# 2_NZPP.net
KiCad netlist of a schematic drawn in Altium Designer
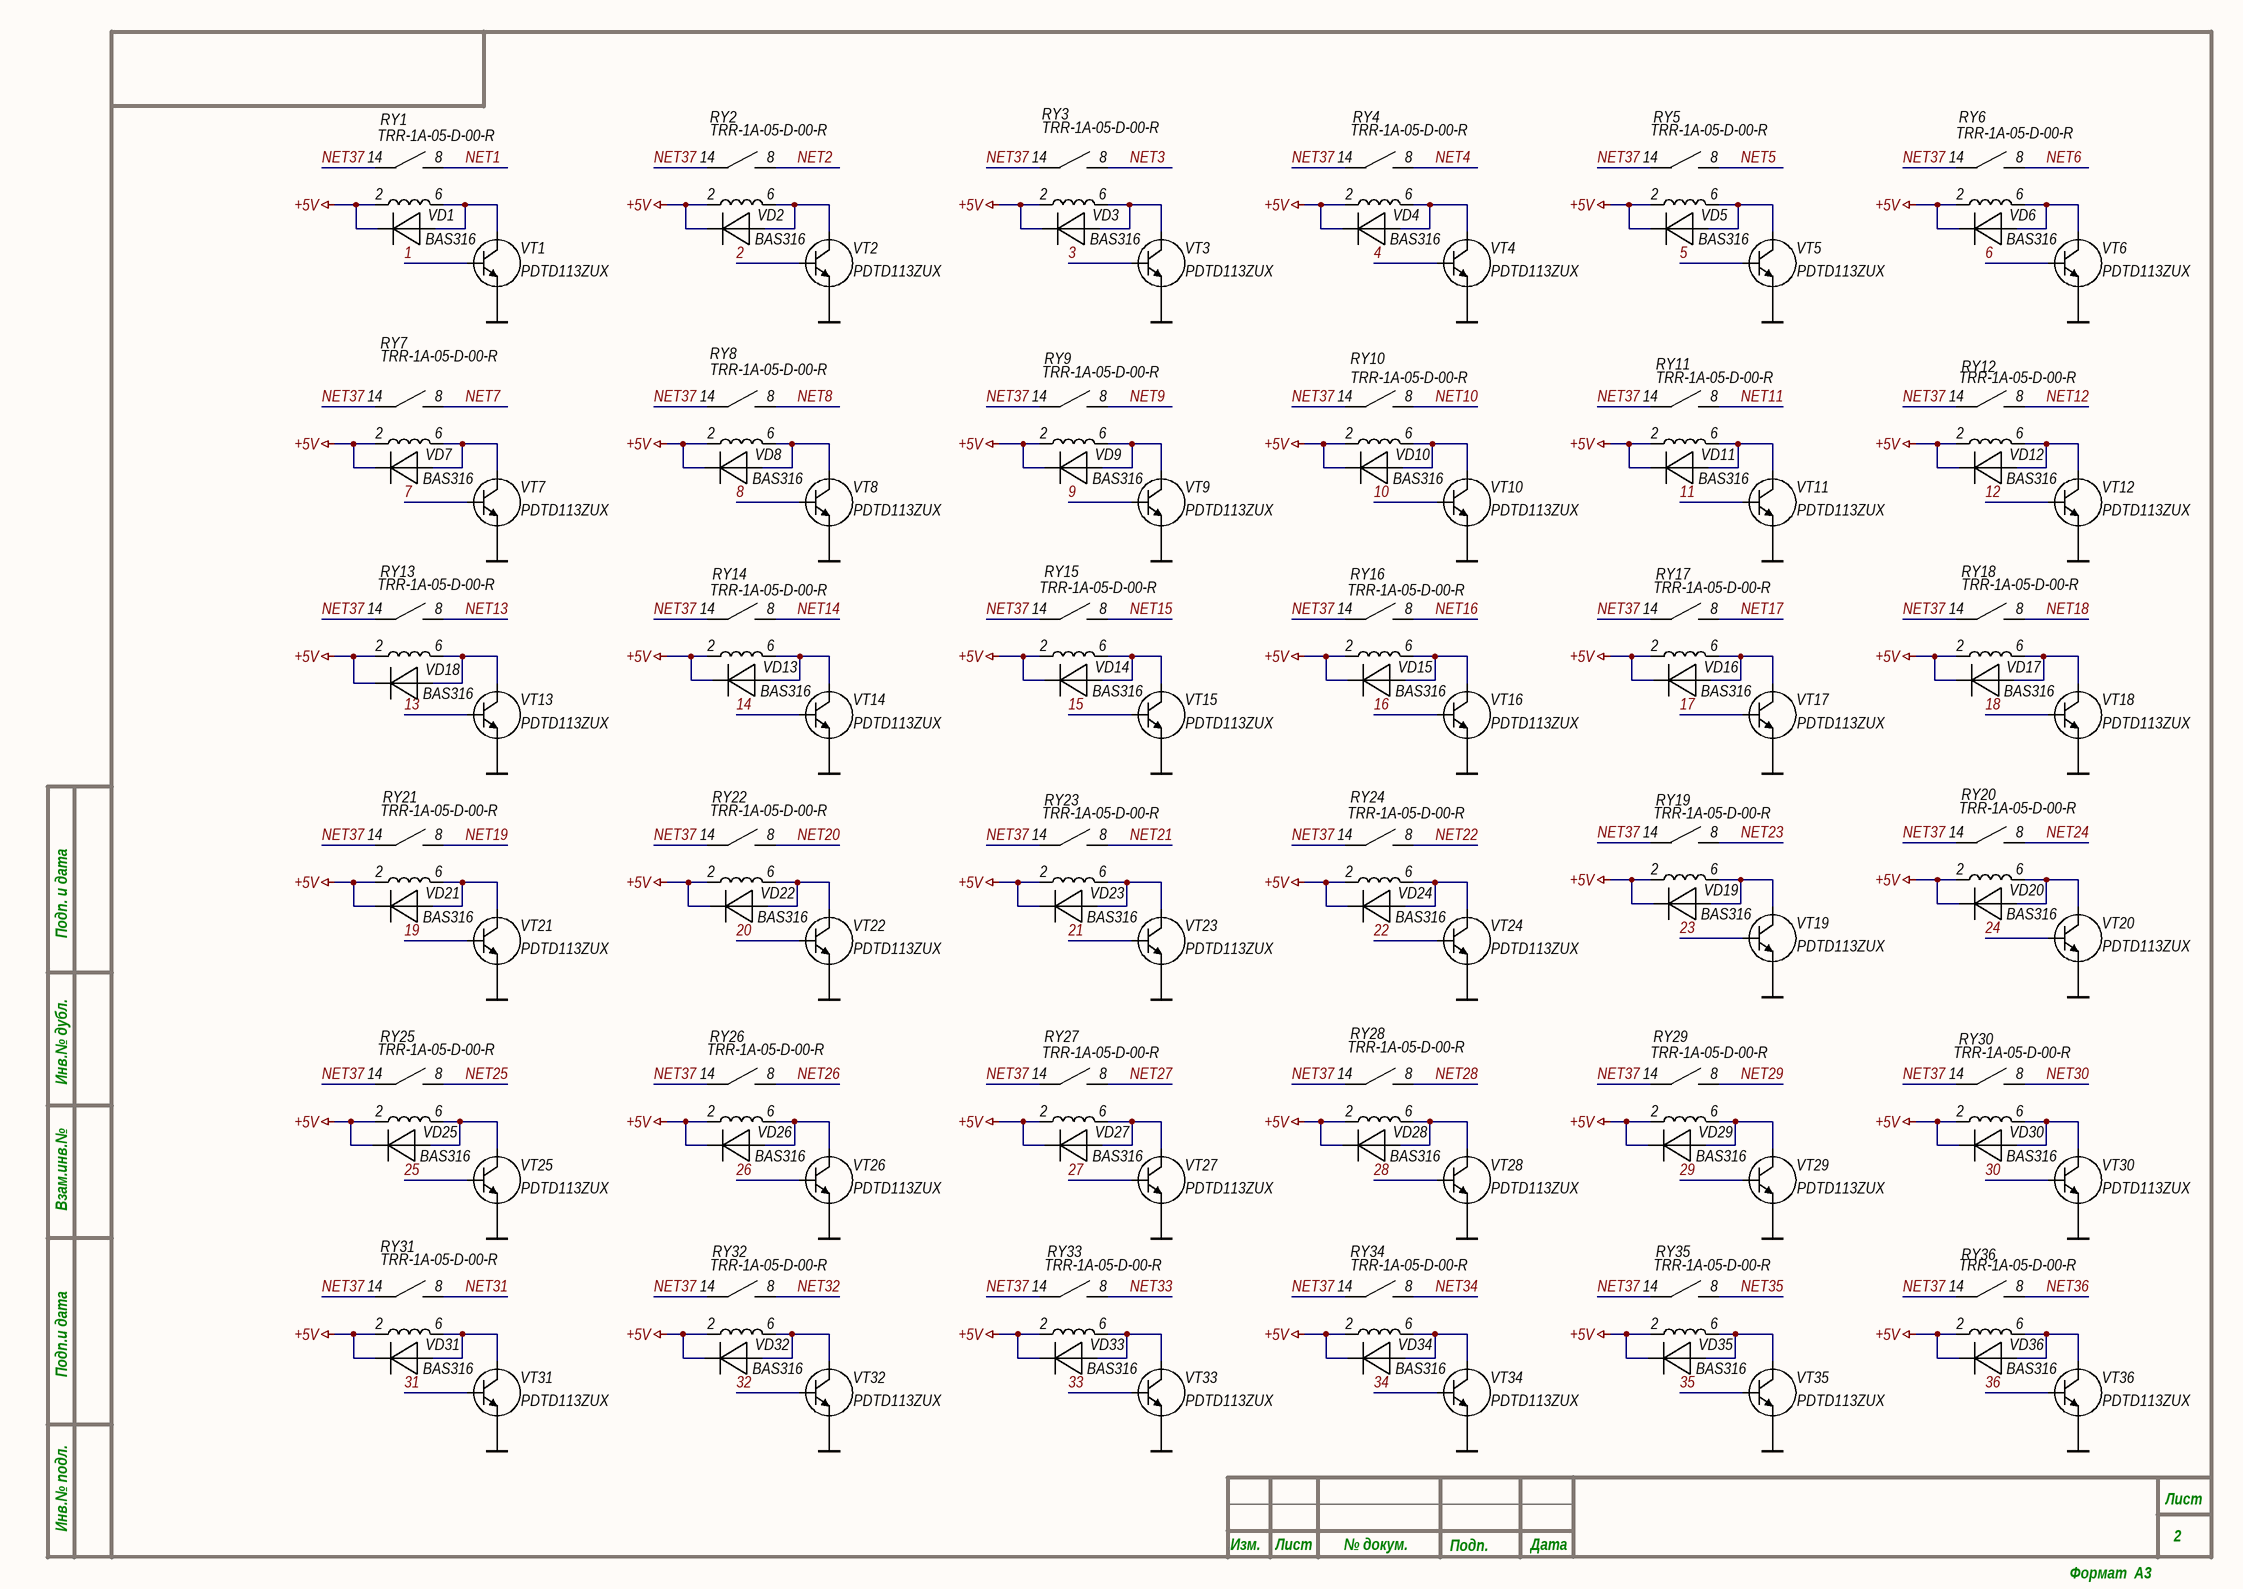
[diagram p0: 2.NZPP.SchDoc]

(export (version "E")
  (design (tool "Eeschema 10.0.6"))
  (components
    (comp (ref "RY1")
      (value "TRR-1A-05-D-00-R")
      (footprint "TRR-1A-05-D-00-R")
      (libsource (lib "Schlib1") (part "TRR-1A-05-D-00-R"))
    )
    (comp (ref "RY2")
      (value "TRR-1A-05-D-00-R")
      (footprint "TRR-1A-05-D-00-R")
      (libsource (lib "Schlib1") (part "TRR-1A-05-D-00-R"))
    )
    (comp (ref "RY3")
      (value "TRR-1A-05-D-00-R")
      (footprint "TRR-1A-05-D-00-R")
      (libsource (lib "Schlib1") (part "TRR-1A-05-D-00-R"))
    )
    (comp (ref "RY4")
      (value "TRR-1A-05-D-00-R")
      (footprint "TRR-1A-05-D-00-R")
      (libsource (lib "Schlib1") (part "TRR-1A-05-D-00-R"))
    )
    (comp (ref "RY5")
      (value "TRR-1A-05-D-00-R")
      (footprint "TRR-1A-05-D-00-R")
      (libsource (lib "Schlib1") (part "TRR-1A-05-D-00-R"))
    )
    (comp (ref "RY6")
      (value "TRR-1A-05-D-00-R")
      (footprint "TRR-1A-05-D-00-R")
      (libsource (lib "") (part "TRR-1A-05-D-00-R_1"))
    )
    (comp (ref "RY7")
      (value "TRR-1A-05-D-00-R")
      (footprint "TRR-1A-05-D-00-R")
      (libsource (lib "Schlib1") (part "TRR-1A-05-D-00-R"))
    )
    (comp (ref "RY8")
      (value "TRR-1A-05-D-00-R")
      (footprint "TRR-1A-05-D-00-R")
      (libsource (lib "Schlib1") (part "TRR-1A-05-D-00-R"))
    )
    (comp (ref "RY9")
      (value "TRR-1A-05-D-00-R")
      (footprint "TRR-1A-05-D-00-R")
      (libsource (lib "Schlib1") (part "TRR-1A-05-D-00-R"))
    )
    (comp (ref "RY10")
      (value "TRR-1A-05-D-00-R")
      (footprint "TRR-1A-05-D-00-R")
      (libsource (lib "Schlib1") (part "TRR-1A-05-D-00-R"))
    )
    (comp (ref "RY11")
      (value "TRR-1A-05-D-00-R")
      (footprint "TRR-1A-05-D-00-R")
      (libsource (lib "Schlib1") (part "TRR-1A-05-D-00-R"))
    )
    (comp (ref "RY12")
      (value "TRR-1A-05-D-00-R")
      (footprint "TRR-1A-05-D-00-R")
      (libsource (lib "") (part "TRR-1A-05-D-00-R_1"))
    )
    (comp (ref "RY13")
      (value "TRR-1A-05-D-00-R")
      (footprint "TRR-1A-05-D-00-R")
      (libsource (lib "Schlib1") (part "TRR-1A-05-D-00-R"))
    )
    (comp (ref "RY14")
      (value "TRR-1A-05-D-00-R")
      (footprint "TRR-1A-05-D-00-R")
      (libsource (lib "Schlib1") (part "TRR-1A-05-D-00-R"))
    )
    (comp (ref "RY15")
      (value "TRR-1A-05-D-00-R")
      (footprint "TRR-1A-05-D-00-R")
      (libsource (lib "Schlib1") (part "TRR-1A-05-D-00-R"))
    )
    (comp (ref "RY16")
      (value "TRR-1A-05-D-00-R")
      (footprint "TRR-1A-05-D-00-R")
      (libsource (lib "Schlib1") (part "TRR-1A-05-D-00-R"))
    )
    (comp (ref "RY17")
      (value "TRR-1A-05-D-00-R")
      (footprint "TRR-1A-05-D-00-R")
      (libsource (lib "Schlib1") (part "TRR-1A-05-D-00-R"))
    )
    (comp (ref "RY18")
      (value "TRR-1A-05-D-00-R")
      (footprint "TRR-1A-05-D-00-R")
      (libsource (lib "") (part "TRR-1A-05-D-00-R_1"))
    )
    (comp (ref "RY19")
      (value "TRR-1A-05-D-00-R")
      (footprint "TRR-1A-05-D-00-R")
      (libsource (lib "Schlib1") (part "TRR-1A-05-D-00-R"))
    )
    (comp (ref "RY20")
      (value "TRR-1A-05-D-00-R")
      (footprint "TRR-1A-05-D-00-R")
      (libsource (lib "") (part "TRR-1A-05-D-00-R_1"))
    )
    (comp (ref "RY21")
      (value "TRR-1A-05-D-00-R")
      (footprint "TRR-1A-05-D-00-R")
      (libsource (lib "Schlib1") (part "TRR-1A-05-D-00-R"))
    )
    (comp (ref "RY22")
      (value "TRR-1A-05-D-00-R")
      (footprint "TRR-1A-05-D-00-R")
      (libsource (lib "Schlib1") (part "TRR-1A-05-D-00-R"))
    )
    (comp (ref "RY23")
      (value "TRR-1A-05-D-00-R")
      (footprint "TRR-1A-05-D-00-R")
      (libsource (lib "Schlib1") (part "TRR-1A-05-D-00-R"))
    )
    (comp (ref "RY24")
      (value "TRR-1A-05-D-00-R")
      (footprint "TRR-1A-05-D-00-R")
      (libsource (lib "Schlib1") (part "TRR-1A-05-D-00-R"))
    )
    (comp (ref "RY25")
      (value "TRR-1A-05-D-00-R")
      (footprint "TRR-1A-05-D-00-R")
      (libsource (lib "Schlib1") (part "TRR-1A-05-D-00-R"))
    )
    (comp (ref "RY26")
      (value "TRR-1A-05-D-00-R")
      (footprint "TRR-1A-05-D-00-R")
      (libsource (lib "Schlib1") (part "TRR-1A-05-D-00-R"))
    )
    (comp (ref "RY27")
      (value "TRR-1A-05-D-00-R")
      (footprint "TRR-1A-05-D-00-R")
      (libsource (lib "Schlib1") (part "TRR-1A-05-D-00-R"))
    )
    (comp (ref "RY28")
      (value "TRR-1A-05-D-00-R")
      (footprint "TRR-1A-05-D-00-R")
      (libsource (lib "Schlib1") (part "TRR-1A-05-D-00-R"))
    )
    (comp (ref "RY29")
      (value "TRR-1A-05-D-00-R")
      (footprint "TRR-1A-05-D-00-R")
      (libsource (lib "Schlib1") (part "TRR-1A-05-D-00-R"))
    )
    (comp (ref "RY30")
      (value "TRR-1A-05-D-00-R")
      (footprint "TRR-1A-05-D-00-R")
      (libsource (lib "") (part "TRR-1A-05-D-00-R_1"))
    )
    (comp (ref "RY31")
      (value "TRR-1A-05-D-00-R")
      (footprint "TRR-1A-05-D-00-R")
      (libsource (lib "Schlib1") (part "TRR-1A-05-D-00-R"))
    )
    (comp (ref "RY32")
      (value "TRR-1A-05-D-00-R")
      (footprint "TRR-1A-05-D-00-R")
      (libsource (lib "Schlib1") (part "TRR-1A-05-D-00-R"))
    )
    (comp (ref "RY33")
      (value "TRR-1A-05-D-00-R")
      (footprint "TRR-1A-05-D-00-R")
      (libsource (lib "Schlib1") (part "TRR-1A-05-D-00-R"))
    )
    (comp (ref "RY34")
      (value "TRR-1A-05-D-00-R")
      (footprint "TRR-1A-05-D-00-R")
      (libsource (lib "Schlib1") (part "TRR-1A-05-D-00-R"))
    )
    (comp (ref "RY35")
      (value "TRR-1A-05-D-00-R")
      (footprint "TRR-1A-05-D-00-R")
      (libsource (lib "Schlib1") (part "TRR-1A-05-D-00-R"))
    )
    (comp (ref "RY36")
      (value "TRR-1A-05-D-00-R")
      (footprint "TRR-1A-05-D-00-R")
      (libsource (lib "") (part "TRR-1A-05-D-00-R_1"))
    )
    (comp (ref "VD1")
      (value "BAS316")
      (footprint "DIODE: SOD323")
      (libsource (lib "diode") (part "Diode_single"))
    )
    (comp (ref "VD2")
      (value "BAS316")
      (footprint "DIODE: SOD323")
      (libsource (lib "diode") (part "Diode_single"))
    )
    (comp (ref "VD3")
      (value "BAS316")
      (footprint "DIODE: SOD323")
      (libsource (lib "diode") (part "Diode_single"))
    )
    (comp (ref "VD4")
      (value "BAS316")
      (footprint "DIODE: SOD323")
      (libsource (lib "diode") (part "Diode_single"))
    )
    (comp (ref "VD5")
      (value "BAS316")
      (footprint "DIODE: SOD323")
      (libsource (lib "diode") (part "Diode_single"))
    )
    (comp (ref "VD6")
      (value "BAS316")
      (footprint "DIODE: SOD323")
      (libsource (lib "diode") (part "Diode_single"))
    )
    (comp (ref "VD7")
      (value "BAS316")
      (footprint "DIODE: SOD323")
      (libsource (lib "diode") (part "Diode_single"))
    )
    (comp (ref "VD8")
      (value "BAS316")
      (footprint "DIODE: SOD323")
      (libsource (lib "diode") (part "Diode_single"))
    )
    (comp (ref "VD9")
      (value "BAS316")
      (footprint "DIODE: SOD323")
      (libsource (lib "diode") (part "Diode_single"))
    )
    (comp (ref "VD10")
      (value "BAS316")
      (footprint "DIODE: SOD323")
      (libsource (lib "diode") (part "Diode_single"))
    )
    (comp (ref "VD11")
      (value "BAS316")
      (footprint "DIODE: SOD323")
      (libsource (lib "diode") (part "Diode_single"))
    )
    (comp (ref "VD12")
      (value "BAS316")
      (footprint "DIODE: SOD323")
      (libsource (lib "diode") (part "Diode_single"))
    )
    (comp (ref "VD13")
      (value "BAS316")
      (footprint "DIODE: SOD323")
      (libsource (lib "diode") (part "Diode_single"))
    )
    (comp (ref "VD14")
      (value "BAS316")
      (footprint "DIODE: SOD323")
      (libsource (lib "diode") (part "Diode_single"))
    )
    (comp (ref "VD15")
      (value "BAS316")
      (footprint "DIODE: SOD323")
      (libsource (lib "diode") (part "Diode_single"))
    )
    (comp (ref "VD16")
      (value "BAS316")
      (footprint "DIODE: SOD323")
      (libsource (lib "diode") (part "Diode_single"))
    )
    (comp (ref "VD17")
      (value "BAS316")
      (footprint "DIODE: SOD323")
      (libsource (lib "diode") (part "Diode_single"))
    )
    (comp (ref "VD18")
      (value "BAS316")
      (footprint "DIODE: SOD323")
      (libsource (lib "diode") (part "Diode_single"))
    )
    (comp (ref "VD19")
      (value "BAS316")
      (footprint "DIODE: SOD323")
      (libsource (lib "diode") (part "Diode_single"))
    )
    (comp (ref "VD20")
      (value "BAS316")
      (footprint "DIODE: SOD323")
      (libsource (lib "diode") (part "Diode_single"))
    )
    (comp (ref "VD21")
      (value "BAS316")
      (footprint "DIODE: SOD323")
      (libsource (lib "diode") (part "Diode_single"))
    )
    (comp (ref "VD22")
      (value "BAS316")
      (footprint "DIODE: SOD323")
      (libsource (lib "diode") (part "Diode_single"))
    )
    (comp (ref "VD23")
      (value "BAS316")
      (footprint "DIODE: SOD323")
      (libsource (lib "diode") (part "Diode_single"))
    )
    (comp (ref "VD24")
      (value "BAS316")
      (footprint "DIODE: SOD323")
      (libsource (lib "diode") (part "Diode_single"))
    )
    (comp (ref "VD25")
      (value "BAS316")
      (footprint "DIODE: SOD323")
      (libsource (lib "diode") (part "Diode_single"))
    )
    (comp (ref "VD26")
      (value "BAS316")
      (footprint "DIODE: SOD323")
      (libsource (lib "diode") (part "Diode_single"))
    )
    (comp (ref "VD27")
      (value "BAS316")
      (footprint "DIODE: SOD323")
      (libsource (lib "diode") (part "Diode_single"))
    )
    (comp (ref "VD28")
      (value "BAS316")
      (footprint "DIODE: SOD323")
      (libsource (lib "") (part "Diode_single_1"))
    )
    (comp (ref "VD29")
      (value "BAS316")
      (footprint "DIODE: SOD323")
      (libsource (lib "diode") (part "Diode_single"))
    )
    (comp (ref "VD30")
      (value "BAS316")
      (footprint "DIODE: SOD323")
      (libsource (lib "diode") (part "Diode_single"))
    )
    (comp (ref "VD31")
      (value "BAS316")
      (footprint "DIODE: SOD323")
      (libsource (lib "diode") (part "Diode_single"))
    )
    (comp (ref "VD32")
      (value "BAS316")
      (footprint "DIODE: SOD323")
      (libsource (lib "diode") (part "Diode_single"))
    )
    (comp (ref "VD33")
      (value "BAS316")
      (footprint "DIODE: SOD323")
      (libsource (lib "diode") (part "Diode_single"))
    )
    (comp (ref "VD34")
      (value "BAS316")
      (footprint "DIODE: SOD323")
      (libsource (lib "diode") (part "Diode_single"))
    )
    (comp (ref "VD35")
      (value "BAS316")
      (footprint "DIODE: SOD323")
      (libsource (lib "diode") (part "Diode_single"))
    )
    (comp (ref "VD36")
      (value "BAS316")
      (footprint "DIODE: SOD323")
      (libsource (lib "diode") (part "Diode_single"))
    )
    (comp (ref "VT1")
      (value "PDTD113ZUX")
      (footprint "SC-70")
      (fields
        (field (name "MANUFACTURER") "ON Semiconductor")
        (field (name "VALUEMANUFACTURERPARTNUMBER") "NPN transistor, 45V, 100mA, 100MHz, 300mW, 0.6V, 420, SOT-23, -55...+125°C")
        (field (name "PARTNUMBER") "PDTD113ZUX")
      )
      (libsource (lib "transistor") (part "BJT_NPN_132"))
    )
    (comp (ref "VT2")
      (value "PDTD113ZUX")
      (footprint "SC-70")
      (fields
        (field (name "MANUFACTURER") "ON Semiconductor")
        (field (name "VALUEMANUFACTURERPARTNUMBER") "NPN transistor, 45V, 100mA, 100MHz, 300mW, 0.6V, 420, SOT-23, -55...+125°C")
        (field (name "PARTNUMBER") "PDTD113ZUX")
      )
      (libsource (lib "transistor") (part "BJT_NPN_132"))
    )
    (comp (ref "VT3")
      (value "PDTD113ZUX")
      (footprint "SC-70")
      (fields
        (field (name "MANUFACTURER") "ON Semiconductor")
        (field (name "VALUEMANUFACTURERPARTNUMBER") "NPN transistor, 45V, 100mA, 100MHz, 300mW, 0.6V, 420, SOT-23, -55...+125°C")
        (field (name "PARTNUMBER") "PDTD113ZUX")
      )
      (libsource (lib "transistor") (part "BJT_NPN_132"))
    )
    (comp (ref "VT4")
      (value "PDTD113ZUX")
      (footprint "SC-70")
      (fields
        (field (name "MANUFACTURER") "ON Semiconductor")
        (field (name "VALUEMANUFACTURERPARTNUMBER") "NPN transistor, 45V, 100mA, 100MHz, 300mW, 0.6V, 420, SOT-23, -55...+125°C")
        (field (name "PARTNUMBER") "PDTD113ZUX")
      )
      (libsource (lib "transistor") (part "BJT_NPN_132"))
    )
    (comp (ref "VT5")
      (value "PDTD113ZUX")
      (footprint "SC-70")
      (fields
        (field (name "MANUFACTURER") "ON Semiconductor")
        (field (name "VALUEMANUFACTURERPARTNUMBER") "NPN transistor, 45V, 100mA, 100MHz, 300mW, 0.6V, 420, SOT-23, -55...+125°C")
        (field (name "PARTNUMBER") "PDTD113ZUX")
      )
      (libsource (lib "transistor") (part "BJT_NPN_132"))
    )
    (comp (ref "VT6")
      (value "PDTD113ZUX")
      (footprint "SC-70")
      (fields
        (field (name "MANUFACTURER") "ON Semiconductor")
        (field (name "VALUEMANUFACTURERPARTNUMBER") "NPN transistor, 45V, 100mA, 100MHz, 300mW, 0.6V, 420, SOT-23, -55...+125°C")
        (field (name "PARTNUMBER") "PDTD113ZUX")
      )
      (libsource (lib "transistor") (part "BJT_NPN_132"))
    )
    (comp (ref "VT7")
      (value "PDTD113ZUX")
      (footprint "SC-70")
      (fields
        (field (name "MANUFACTURER") "ON Semiconductor")
        (field (name "VALUEMANUFACTURERPARTNUMBER") "NPN transistor, 45V, 100mA, 100MHz, 300mW, 0.6V, 420, SOT-23, -55...+125°C")
        (field (name "PARTNUMBER") "PDTD113ZUX")
      )
      (libsource (lib "transistor") (part "BJT_NPN_132"))
    )
    (comp (ref "VT8")
      (value "PDTD113ZUX")
      (footprint "SC-70")
      (fields
        (field (name "MANUFACTURER") "ON Semiconductor")
        (field (name "VALUEMANUFACTURERPARTNUMBER") "NPN transistor, 45V, 100mA, 100MHz, 300mW, 0.6V, 420, SOT-23, -55...+125°C")
        (field (name "PARTNUMBER") "PDTD113ZUX")
      )
      (libsource (lib "transistor") (part "BJT_NPN_132"))
    )
    (comp (ref "VT9")
      (value "PDTD113ZUX")
      (footprint "SC-70")
      (fields
        (field (name "MANUFACTURER") "ON Semiconductor")
        (field (name "VALUEMANUFACTURERPARTNUMBER") "NPN transistor, 45V, 100mA, 100MHz, 300mW, 0.6V, 420, SOT-23, -55...+125°C")
        (field (name "PARTNUMBER") "PDTD113ZUX")
      )
      (libsource (lib "transistor") (part "BJT_NPN_132"))
    )
    (comp (ref "VT10")
      (value "PDTD113ZUX")
      (footprint "SC-70")
      (fields
        (field (name "MANUFACTURER") "ON Semiconductor")
        (field (name "VALUEMANUFACTURERPARTNUMBER") "NPN transistor, 45V, 100mA, 100MHz, 300mW, 0.6V, 420, SOT-23, -55...+125°C")
        (field (name "PARTNUMBER") "PDTD113ZUX")
      )
      (libsource (lib "transistor") (part "BJT_NPN_132"))
    )
    (comp (ref "VT11")
      (value "PDTD113ZUX")
      (footprint "SC-70")
      (fields
        (field (name "MANUFACTURER") "ON Semiconductor")
        (field (name "VALUEMANUFACTURERPARTNUMBER") "NPN transistor, 45V, 100mA, 100MHz, 300mW, 0.6V, 420, SOT-23, -55...+125°C")
        (field (name "PARTNUMBER") "PDTD113ZUX")
      )
      (libsource (lib "transistor") (part "BJT_NPN_132"))
    )
    (comp (ref "VT12")
      (value "PDTD113ZUX")
      (footprint "SC-70")
      (fields
        (field (name "MANUFACTURER") "ON Semiconductor")
        (field (name "VALUEMANUFACTURERPARTNUMBER") "NPN transistor, 45V, 100mA, 100MHz, 300mW, 0.6V, 420, SOT-23, -55...+125°C")
        (field (name "PARTNUMBER") "PDTD113ZUX")
      )
      (libsource (lib "transistor") (part "BJT_NPN_132"))
    )
    (comp (ref "VT13")
      (value "PDTD113ZUX")
      (footprint "SC-70")
      (fields
        (field (name "MANUFACTURER") "ON Semiconductor")
        (field (name "VALUEMANUFACTURERPARTNUMBER") "NPN transistor, 45V, 100mA, 100MHz, 300mW, 0.6V, 420, SOT-23, -55...+125°C")
        (field (name "PARTNUMBER") "PDTD113ZUX")
      )
      (libsource (lib "transistor") (part "BJT_NPN_132"))
    )
    (comp (ref "VT14")
      (value "PDTD113ZUX")
      (footprint "SC-70")
      (fields
        (field (name "MANUFACTURER") "ON Semiconductor")
        (field (name "VALUEMANUFACTURERPARTNUMBER") "NPN transistor, 45V, 100mA, 100MHz, 300mW, 0.6V, 420, SOT-23, -55...+125°C")
        (field (name "PARTNUMBER") "PDTD113ZUX")
      )
      (libsource (lib "transistor") (part "BJT_NPN_132"))
    )
    (comp (ref "VT15")
      (value "PDTD113ZUX")
      (footprint "SC-70")
      (fields
        (field (name "MANUFACTURER") "ON Semiconductor")
        (field (name "VALUEMANUFACTURERPARTNUMBER") "NPN transistor, 45V, 100mA, 100MHz, 300mW, 0.6V, 420, SOT-23, -55...+125°C")
        (field (name "PARTNUMBER") "PDTD113ZUX")
      )
      (libsource (lib "transistor") (part "BJT_NPN_132"))
    )
    (comp (ref "VT16")
      (value "PDTD113ZUX")
      (footprint "SC-70")
      (fields
        (field (name "MANUFACTURER") "ON Semiconductor")
        (field (name "VALUEMANUFACTURERPARTNUMBER") "NPN transistor, 45V, 100mA, 100MHz, 300mW, 0.6V, 420, SOT-23, -55...+125°C")
        (field (name "PARTNUMBER") "PDTD113ZUX")
      )
      (libsource (lib "transistor") (part "BJT_NPN_132"))
    )
    (comp (ref "VT17")
      (value "PDTD113ZUX")
      (footprint "SC-70")
      (fields
        (field (name "MANUFACTURER") "ON Semiconductor")
        (field (name "VALUEMANUFACTURERPARTNUMBER") "NPN transistor, 45V, 100mA, 100MHz, 300mW, 0.6V, 420, SOT-23, -55...+125°C")
        (field (name "PARTNUMBER") "PDTD113ZUX")
      )
      (libsource (lib "transistor") (part "BJT_NPN_132"))
    )
    (comp (ref "VT18")
      (value "PDTD113ZUX")
      (footprint "SC-70")
      (fields
        (field (name "MANUFACTURER") "ON Semiconductor")
        (field (name "VALUEMANUFACTURERPARTNUMBER") "NPN transistor, 45V, 100mA, 100MHz, 300mW, 0.6V, 420, SOT-23, -55...+125°C")
        (field (name "PARTNUMBER") "PDTD113ZUX")
      )
      (libsource (lib "transistor") (part "BJT_NPN_132"))
    )
    (comp (ref "VT19")
      (value "PDTD113ZUX")
      (footprint "SC-70")
      (fields
        (field (name "MANUFACTURER") "ON Semiconductor")
        (field (name "VALUEMANUFACTURERPARTNUMBER") "NPN transistor, 45V, 100mA, 100MHz, 300mW, 0.6V, 420, SOT-23, -55...+125°C")
        (field (name "PARTNUMBER") "PDTD113ZUX")
      )
      (libsource (lib "transistor") (part "BJT_NPN_132"))
    )
    (comp (ref "VT20")
      (value "PDTD113ZUX")
      (footprint "SC-70")
      (fields
        (field (name "MANUFACTURER") "ON Semiconductor")
        (field (name "VALUEMANUFACTURERPARTNUMBER") "NPN transistor, 45V, 100mA, 100MHz, 300mW, 0.6V, 420, SOT-23, -55...+125°C")
        (field (name "PARTNUMBER") "PDTD113ZUX")
      )
      (libsource (lib "transistor") (part "BJT_NPN_132"))
    )
    (comp (ref "VT21")
      (value "PDTD113ZUX")
      (footprint "SC-70")
      (fields
        (field (name "MANUFACTURER") "ON Semiconductor")
        (field (name "VALUEMANUFACTURERPARTNUMBER") "NPN transistor, 45V, 100mA, 100MHz, 300mW, 0.6V, 420, SOT-23, -55...+125°C")
        (field (name "PARTNUMBER") "PDTD113ZUX")
      )
      (libsource (lib "transistor") (part "BJT_NPN_132"))
    )
    (comp (ref "VT22")
      (value "PDTD113ZUX")
      (footprint "SC-70")
      (fields
        (field (name "MANUFACTURER") "ON Semiconductor")
        (field (name "VALUEMANUFACTURERPARTNUMBER") "NPN transistor, 45V, 100mA, 100MHz, 300mW, 0.6V, 420, SOT-23, -55...+125°C")
        (field (name "PARTNUMBER") "PDTD113ZUX")
      )
      (libsource (lib "transistor") (part "BJT_NPN_132"))
    )
    (comp (ref "VT23")
      (value "PDTD113ZUX")
      (footprint "SC-70")
      (fields
        (field (name "MANUFACTURER") "ON Semiconductor")
        (field (name "VALUEMANUFACTURERPARTNUMBER") "NPN transistor, 45V, 100mA, 100MHz, 300mW, 0.6V, 420, SOT-23, -55...+125°C")
        (field (name "PARTNUMBER") "PDTD113ZUX")
      )
      (libsource (lib "transistor") (part "BJT_NPN_132"))
    )
    (comp (ref "VT24")
      (value "PDTD113ZUX")
      (footprint "SC-70")
      (fields
        (field (name "MANUFACTURER") "ON Semiconductor")
        (field (name "VALUEMANUFACTURERPARTNUMBER") "NPN transistor, 45V, 100mA, 100MHz, 300mW, 0.6V, 420, SOT-23, -55...+125°C")
        (field (name "PARTNUMBER") "PDTD113ZUX")
      )
      (libsource (lib "transistor") (part "BJT_NPN_132"))
    )
    (comp (ref "VT25")
      (value "PDTD113ZUX")
      (footprint "SC-70")
      (fields
        (field (name "MANUFACTURER") "ON Semiconductor")
        (field (name "VALUEMANUFACTURERPARTNUMBER") "NPN transistor, 45V, 100mA, 100MHz, 300mW, 0.6V, 420, SOT-23, -55...+125°C")
        (field (name "PARTNUMBER") "PDTD113ZUX")
      )
      (libsource (lib "transistor") (part "BJT_NPN_132"))
    )
    (comp (ref "VT26")
      (value "PDTD113ZUX")
      (footprint "SC-70")
      (fields
        (field (name "MANUFACTURER") "ON Semiconductor")
        (field (name "VALUEMANUFACTURERPARTNUMBER") "NPN transistor, 45V, 100mA, 100MHz, 300mW, 0.6V, 420, SOT-23, -55...+125°C")
        (field (name "PARTNUMBER") "PDTD113ZUX")
      )
      (libsource (lib "transistor") (part "BJT_NPN_132"))
    )
    (comp (ref "VT27")
      (value "PDTD113ZUX")
      (footprint "SC-70")
      (fields
        (field (name "MANUFACTURER") "ON Semiconductor")
        (field (name "VALUEMANUFACTURERPARTNUMBER") "NPN transistor, 45V, 100mA, 100MHz, 300mW, 0.6V, 420, SOT-23, -55...+125°C")
        (field (name "PARTNUMBER") "PDTD113ZUX")
      )
      (libsource (lib "transistor") (part "BJT_NPN_132"))
    )
    (comp (ref "VT28")
      (value "PDTD113ZUX")
      (footprint "SC-70")
      (fields
        (field (name "MANUFACTURER") "ON Semiconductor")
        (field (name "VALUEMANUFACTURERPARTNUMBER") "NPN transistor, 45V, 100mA, 100MHz, 300mW, 0.6V, 420, SOT-23, -55...+125°C")
        (field (name "PARTNUMBER") "PDTD113ZUX")
      )
      (libsource (lib "transistor") (part "BJT_NPN_132"))
    )
    (comp (ref "VT29")
      (value "PDTD113ZUX")
      (footprint "SC-70")
      (fields
        (field (name "MANUFACTURER") "ON Semiconductor")
        (field (name "VALUEMANUFACTURERPARTNUMBER") "NPN transistor, 45V, 100mA, 100MHz, 300mW, 0.6V, 420, SOT-23, -55...+125°C")
        (field (name "PARTNUMBER") "PDTD113ZUX")
      )
      (libsource (lib "transistor") (part "BJT_NPN_132"))
    )
    (comp (ref "VT30")
      (value "PDTD113ZUX")
      (footprint "SC-70")
      (fields
        (field (name "MANUFACTURER") "ON Semiconductor")
        (field (name "VALUEMANUFACTURERPARTNUMBER") "NPN transistor, 45V, 100mA, 100MHz, 300mW, 0.6V, 420, SOT-23, -55...+125°C")
        (field (name "PARTNUMBER") "PDTD113ZUX")
      )
      (libsource (lib "transistor") (part "BJT_NPN_132"))
    )
    (comp (ref "VT31")
      (value "PDTD113ZUX")
      (footprint "SC-70")
      (fields
        (field (name "MANUFACTURER") "ON Semiconductor")
        (field (name "VALUEMANUFACTURERPARTNUMBER") "NPN transistor, 45V, 100mA, 100MHz, 300mW, 0.6V, 420, SOT-23, -55...+125°C")
        (field (name "PARTNUMBER") "PDTD113ZUX")
      )
      (libsource (lib "transistor") (part "BJT_NPN_132"))
    )
    (comp (ref "VT32")
      (value "PDTD113ZUX")
      (footprint "SC-70")
      (fields
        (field (name "MANUFACTURER") "ON Semiconductor")
        (field (name "VALUEMANUFACTURERPARTNUMBER") "NPN transistor, 45V, 100mA, 100MHz, 300mW, 0.6V, 420, SOT-23, -55...+125°C")
        (field (name "PARTNUMBER") "PDTD113ZUX")
      )
      (libsource (lib "transistor") (part "BJT_NPN_132"))
    )
    (comp (ref "VT33")
      (value "PDTD113ZUX")
      (footprint "SC-70")
      (fields
        (field (name "MANUFACTURER") "ON Semiconductor")
        (field (name "VALUEMANUFACTURERPARTNUMBER") "NPN transistor, 45V, 100mA, 100MHz, 300mW, 0.6V, 420, SOT-23, -55...+125°C")
        (field (name "PARTNUMBER") "PDTD113ZUX")
      )
      (libsource (lib "transistor") (part "BJT_NPN_132"))
    )
    (comp (ref "VT34")
      (value "PDTD113ZUX")
      (footprint "SC-70")
      (fields
        (field (name "MANUFACTURER") "ON Semiconductor")
        (field (name "VALUEMANUFACTURERPARTNUMBER") "NPN transistor, 45V, 100mA, 100MHz, 300mW, 0.6V, 420, SOT-23, -55...+125°C")
        (field (name "PARTNUMBER") "PDTD113ZUX")
      )
      (libsource (lib "transistor") (part "BJT_NPN_132"))
    )
    (comp (ref "VT35")
      (value "PDTD113ZUX")
      (footprint "SC-70")
      (fields
        (field (name "MANUFACTURER") "ON Semiconductor")
        (field (name "VALUEMANUFACTURERPARTNUMBER") "NPN transistor, 45V, 100mA, 100MHz, 300mW, 0.6V, 420, SOT-23, -55...+125°C")
        (field (name "PARTNUMBER") "PDTD113ZUX")
      )
      (libsource (lib "transistor") (part "BJT_NPN_132"))
    )
    (comp (ref "VT36")
      (value "PDTD113ZUX")
      (footprint "SC-70")
      (fields
        (field (name "MANUFACTURER") "ON Semiconductor")
        (field (name "VALUEMANUFACTURERPARTNUMBER") "NPN transistor, 45V, 100mA, 100MHz, 300mW, 0.6V, 420, SOT-23, -55...+125°C")
        (field (name "PARTNUMBER") "PDTD113ZUX")
      )
      (libsource (lib "transistor") (part "BJT_NPN_132"))
    )
  )
  (nets
    (net (code "1") (name "+5V") (class "Default")
      (node (ref "RY1") (pin "2") (pintype "passive"))
      (node (ref "RY10") (pin "2") (pintype "passive"))
      (node (ref "RY11") (pin "2") (pintype "passive"))
      (node (ref "RY12") (pin "2") (pintype "passive"))
      (node (ref "RY13") (pin "2") (pintype "passive"))
      (node (ref "RY14") (pin "2") (pintype "passive"))
      (node (ref "RY15") (pin "2") (pintype "passive"))
      (node (ref "RY16") (pin "2") (pintype "passive"))
      (node (ref "RY17") (pin "2") (pintype "passive"))
      (node (ref "RY18") (pin "2") (pintype "passive"))
      (node (ref "RY19") (pin "2") (pintype "passive"))
      (node (ref "RY2") (pin "2") (pintype "passive"))
      (node (ref "RY20") (pin "2") (pintype "passive"))
      (node (ref "RY21") (pin "2") (pintype "passive"))
      (node (ref "RY22") (pin "2") (pintype "passive"))
      (node (ref "RY23") (pin "2") (pintype "passive"))
      (node (ref "RY24") (pin "2") (pintype "passive"))
      (node (ref "RY25") (pin "2") (pintype "passive"))
      (node (ref "RY26") (pin "2") (pintype "passive"))
      (node (ref "RY27") (pin "2") (pintype "passive"))
      (node (ref "RY28") (pin "2") (pintype "passive"))
      (node (ref "RY29") (pin "2") (pintype "passive"))
      (node (ref "RY3") (pin "2") (pintype "passive"))
      (node (ref "RY30") (pin "2") (pintype "passive"))
      (node (ref "RY31") (pin "2") (pintype "passive"))
      (node (ref "RY32") (pin "2") (pintype "passive"))
      (node (ref "RY33") (pin "2") (pintype "passive"))
      (node (ref "RY34") (pin "2") (pintype "passive"))
      (node (ref "RY35") (pin "2") (pintype "passive"))
      (node (ref "RY36") (pin "2") (pintype "passive"))
      (node (ref "RY4") (pin "2") (pintype "passive"))
      (node (ref "RY5") (pin "2") (pintype "passive"))
      (node (ref "RY6") (pin "2") (pintype "passive"))
      (node (ref "RY7") (pin "2") (pintype "passive"))
      (node (ref "RY8") (pin "2") (pintype "passive"))
      (node (ref "RY9") (pin "2") (pintype "passive"))
      (node (ref "VD1") (pin "2") (pinfunction "2_2") (pintype "passive"))
      (node (ref "VD10") (pin "2") (pinfunction "2_2") (pintype "passive"))
      (node (ref "VD11") (pin "2") (pinfunction "2_2") (pintype "passive"))
      (node (ref "VD12") (pin "2") (pinfunction "2_2") (pintype "passive"))
      (node (ref "VD13") (pin "2") (pinfunction "2_2") (pintype "passive"))
      (node (ref "VD14") (pin "2") (pinfunction "2_2") (pintype "passive"))
      (node (ref "VD15") (pin "2") (pinfunction "2_2") (pintype "passive"))
      (node (ref "VD16") (pin "2") (pinfunction "2_2") (pintype "passive"))
      (node (ref "VD17") (pin "2") (pinfunction "2_2") (pintype "passive"))
      (node (ref "VD18") (pin "2") (pinfunction "2_2") (pintype "passive"))
      (node (ref "VD19") (pin "2") (pinfunction "2_2") (pintype "passive"))
      (node (ref "VD2") (pin "2") (pinfunction "2_2") (pintype "passive"))
      (node (ref "VD20") (pin "2") (pinfunction "2_2") (pintype "passive"))
      (node (ref "VD21") (pin "2") (pinfunction "2_2") (pintype "passive"))
      (node (ref "VD22") (pin "2") (pinfunction "2_2") (pintype "passive"))
      (node (ref "VD23") (pin "2") (pinfunction "2_2") (pintype "passive"))
      (node (ref "VD24") (pin "2") (pinfunction "2_2") (pintype "passive"))
      (node (ref "VD25") (pin "2") (pinfunction "2_2") (pintype "passive"))
      (node (ref "VD26") (pin "2") (pinfunction "2_2") (pintype "passive"))
      (node (ref "VD27") (pin "2") (pinfunction "2_2") (pintype "passive"))
      (node (ref "VD28") (pin "2") (pinfunction "2_2") (pintype "passive"))
      (node (ref "VD29") (pin "2") (pinfunction "2_2") (pintype "passive"))
      (node (ref "VD3") (pin "2") (pinfunction "2_2") (pintype "passive"))
      (node (ref "VD30") (pin "2") (pinfunction "2_2") (pintype "passive"))
      (node (ref "VD31") (pin "2") (pinfunction "2_2") (pintype "passive"))
      (node (ref "VD32") (pin "2") (pinfunction "2_2") (pintype "passive"))
      (node (ref "VD33") (pin "2") (pinfunction "2_2") (pintype "passive"))
      (node (ref "VD34") (pin "2") (pinfunction "2_2") (pintype "passive"))
      (node (ref "VD35") (pin "2") (pinfunction "2_2") (pintype "passive"))
      (node (ref "VD36") (pin "2") (pinfunction "2_2") (pintype "passive"))
      (node (ref "VD4") (pin "2") (pinfunction "2_2") (pintype "passive"))
      (node (ref "VD5") (pin "2") (pinfunction "2_2") (pintype "passive"))
      (node (ref "VD6") (pin "2") (pinfunction "2_2") (pintype "passive"))
      (node (ref "VD7") (pin "2") (pinfunction "2_2") (pintype "passive"))
      (node (ref "VD8") (pin "2") (pinfunction "2_2") (pintype "passive"))
      (node (ref "VD9") (pin "2") (pinfunction "2_2") (pintype "passive"))
    )
    (net (code "2") (name "/1") (class "Default")
      (node (ref "VT1") (pin "1") (pinfunction "B_1") (pintype "passive"))
    )
    (net (code "3") (name "/2") (class "Default")
      (node (ref "VT2") (pin "1") (pinfunction "B_1") (pintype "passive"))
    )
    (net (code "4") (name "/3") (class "Default")
      (node (ref "VT3") (pin "1") (pinfunction "B_1") (pintype "passive"))
    )
    (net (code "5") (name "/4") (class "Default")
      (node (ref "VT4") (pin "1") (pinfunction "B_1") (pintype "passive"))
    )
    (net (code "6") (name "/5") (class "Default")
      (node (ref "VT5") (pin "1") (pinfunction "B_1") (pintype "passive"))
    )
    (net (code "7") (name "/6") (class "Default")
      (node (ref "VT6") (pin "1") (pinfunction "B_1") (pintype "passive"))
    )
    (net (code "8") (name "/7") (class "Default")
      (node (ref "VT7") (pin "1") (pinfunction "B_1") (pintype "passive"))
    )
    (net (code "9") (name "/8") (class "Default")
      (node (ref "VT8") (pin "1") (pinfunction "B_1") (pintype "passive"))
    )
    (net (code "10") (name "/9") (class "Default")
      (node (ref "VT9") (pin "1") (pinfunction "B_1") (pintype "passive"))
    )
    (net (code "11") (name "/10") (class "Default")
      (node (ref "VT10") (pin "1") (pinfunction "B_1") (pintype "passive"))
    )
    (net (code "12") (name "/11") (class "Default")
      (node (ref "VT11") (pin "1") (pinfunction "B_1") (pintype "passive"))
    )
    (net (code "13") (name "/12") (class "Default")
      (node (ref "VT12") (pin "1") (pinfunction "B_1") (pintype "passive"))
    )
    (net (code "14") (name "/13") (class "Default")
      (node (ref "VT13") (pin "1") (pinfunction "B_1") (pintype "passive"))
    )
    (net (code "15") (name "/14") (class "Default")
      (node (ref "VT14") (pin "1") (pinfunction "B_1") (pintype "passive"))
    )
    (net (code "16") (name "/15") (class "Default")
      (node (ref "VT15") (pin "1") (pinfunction "B_1") (pintype "passive"))
    )
    (net (code "17") (name "/16") (class "Default")
      (node (ref "VT16") (pin "1") (pinfunction "B_1") (pintype "passive"))
    )
    (net (code "18") (name "/17") (class "Default")
      (node (ref "VT17") (pin "1") (pinfunction "B_1") (pintype "passive"))
    )
    (net (code "19") (name "/18") (class "Default")
      (node (ref "VT18") (pin "1") (pinfunction "B_1") (pintype "passive"))
    )
    (net (code "20") (name "/19") (class "Default")
      (node (ref "VT21") (pin "1") (pinfunction "B_1") (pintype "passive"))
    )
    (net (code "21") (name "/20") (class "Default")
      (node (ref "VT22") (pin "1") (pinfunction "B_1") (pintype "passive"))
    )
    (net (code "22") (name "/21") (class "Default")
      (node (ref "VT23") (pin "1") (pinfunction "B_1") (pintype "passive"))
    )
    (net (code "23") (name "/22") (class "Default")
      (node (ref "VT24") (pin "1") (pinfunction "B_1") (pintype "passive"))
    )
    (net (code "24") (name "/23") (class "Default")
      (node (ref "VT19") (pin "1") (pinfunction "B_1") (pintype "passive"))
    )
    (net (code "25") (name "/24") (class "Default")
      (node (ref "VT20") (pin "1") (pinfunction "B_1") (pintype "passive"))
    )
    (net (code "26") (name "/25") (class "Default")
      (node (ref "VT25") (pin "1") (pinfunction "B_1") (pintype "passive"))
    )
    (net (code "27") (name "/26") (class "Default")
      (node (ref "VT26") (pin "1") (pinfunction "B_1") (pintype "passive"))
    )
    (net (code "28") (name "/27") (class "Default")
      (node (ref "VT27") (pin "1") (pinfunction "B_1") (pintype "passive"))
    )
    (net (code "29") (name "/28") (class "Default")
      (node (ref "VT28") (pin "1") (pinfunction "B_1") (pintype "passive"))
    )
    (net (code "30") (name "/29") (class "Default")
      (node (ref "VT29") (pin "1") (pinfunction "B_1") (pintype "passive"))
    )
    (net (code "31") (name "/30") (class "Default")
      (node (ref "VT30") (pin "1") (pinfunction "B_1") (pintype "passive"))
    )
    (net (code "32") (name "/31") (class "Default")
      (node (ref "VT31") (pin "1") (pinfunction "B_1") (pintype "passive"))
    )
    (net (code "33") (name "/32") (class "Default")
      (node (ref "VT32") (pin "1") (pinfunction "B_1") (pintype "passive"))
    )
    (net (code "34") (name "/33") (class "Default")
      (node (ref "VT33") (pin "1") (pinfunction "B_1") (pintype "passive"))
    )
    (net (code "35") (name "/34") (class "Default")
      (node (ref "VT34") (pin "1") (pinfunction "B_1") (pintype "passive"))
    )
    (net (code "36") (name "/35") (class "Default")
      (node (ref "VT35") (pin "1") (pinfunction "B_1") (pintype "passive"))
    )
    (net (code "37") (name "/36") (class "Default")
      (node (ref "VT36") (pin "1") (pinfunction "B_1") (pintype "passive"))
    )
    (net (code "44") (name "/NET1") (class "Default") (node (ref "RY1") (pin "8") (pintype "passive")))
    (net (code "45") (name "/NET2") (class "Default") (node (ref "RY2") (pin "8") (pintype "passive")))
    (net (code "46") (name "/NET3") (class "Default") (node (ref "RY3") (pin "8") (pintype "passive")))
    (net (code "47") (name "/NET4") (class "Default") (node (ref "RY4") (pin "8") (pintype "passive")))
    (net (code "48") (name "/NET5") (class "Default") (node (ref "RY5") (pin "8") (pintype "passive")))
    (net (code "49") (name "/NET6") (class "Default") (node (ref "RY6") (pin "8") (pintype "passive")))
    (net (code "50") (name "/NET7") (class "Default") (node (ref "RY7") (pin "8") (pintype "passive")))
    (net (code "51") (name "/NET8") (class "Default") (node (ref "RY8") (pin "8") (pintype "passive")))
    (net (code "52") (name "/NET9") (class "Default") (node (ref "RY9") (pin "8") (pintype "passive")))
    (net (code "53") (name "/NET10") (class "Default") (node (ref "RY10") (pin "8") (pintype "passive")))
    (net (code "54") (name "/NET11") (class "Default") (node (ref "RY11") (pin "8") (pintype "passive")))
    (net (code "55") (name "/NET12") (class "Default") (node (ref "RY12") (pin "8") (pintype "passive")))
    (net (code "56") (name "/NET13") (class "Default") (node (ref "RY13") (pin "8") (pintype "passive")))
    (net (code "57") (name "/NET14") (class "Default") (node (ref "RY14") (pin "8") (pintype "passive")))
    (net (code "58") (name "/NET15") (class "Default") (node (ref "RY15") (pin "8") (pintype "passive")))
    (net (code "59") (name "/NET16") (class "Default") (node (ref "RY16") (pin "8") (pintype "passive")))
    (net (code "60") (name "/NET17") (class "Default") (node (ref "RY17") (pin "8") (pintype "passive")))
    (net (code "61") (name "/NET18") (class "Default") (node (ref "RY18") (pin "8") (pintype "passive")))
    (net (code "62") (name "/NET19") (class "Default") (node (ref "RY21") (pin "8") (pintype "passive")))
    (net (code "63") (name "/NET20") (class "Default") (node (ref "RY22") (pin "8") (pintype "passive")))
    (net (code "64") (name "/NET21") (class "Default") (node (ref "RY23") (pin "8") (pintype "passive")))
    (net (code "65") (name "/NET22") (class "Default") (node (ref "RY24") (pin "8") (pintype "passive")))
    (net (code "66") (name "/NET23") (class "Default") (node (ref "RY19") (pin "8") (pintype "passive")))
    (net (code "67") (name "/NET24") (class "Default") (node (ref "RY20") (pin "8") (pintype "passive")))
    (net (code "68") (name "/NET25") (class "Default") (node (ref "RY25") (pin "8") (pintype "passive")))
    (net (code "69") (name "/NET26") (class "Default") (node (ref "RY26") (pin "8") (pintype "passive")))
    (net (code "70") (name "/NET27") (class "Default") (node (ref "RY27") (pin "8") (pintype "passive")))
    (net (code "71") (name "/NET28") (class "Default") (node (ref "RY28") (pin "8") (pintype "passive")))
    (net (code "72") (name "/NET29") (class "Default") (node (ref "RY29") (pin "8") (pintype "passive")))
    (net (code "73") (name "/NET30") (class "Default") (node (ref "RY30") (pin "8") (pintype "passive")))
    (net (code "74") (name "/NET31") (class "Default") (node (ref "RY31") (pin "8") (pintype "passive")))
    (net (code "75") (name "/NET32") (class "Default") (node (ref "RY32") (pin "8") (pintype "passive")))
    (net (code "76") (name "/NET33") (class "Default") (node (ref "RY33") (pin "8") (pintype "passive")))
    (net (code "77") (name "/NET34") (class "Default") (node (ref "RY34") (pin "8") (pintype "passive")))
    (net (code "78") (name "/NET35") (class "Default") (node (ref "RY35") (pin "8") (pintype "passive")))
    (net (code "79") (name "/NET36") (class "Default") (node (ref "RY36") (pin "8") (pintype "passive")))
    (net (code "80") (name "/NET37") (class "Default")
      (node (ref "RY1") (pin "14") (pintype "passive"))
      (node (ref "RY10") (pin "14") (pintype "passive"))
      (node (ref "RY11") (pin "14") (pintype "passive"))
      (node (ref "RY12") (pin "14") (pintype "passive"))
      (node (ref "RY13") (pin "14") (pintype "passive"))
      (node (ref "RY14") (pin "14") (pintype "passive"))
      (node (ref "RY15") (pin "14") (pintype "passive"))
      (node (ref "RY16") (pin "14") (pintype "passive"))
      (node (ref "RY17") (pin "14") (pintype "passive"))
      (node (ref "RY18") (pin "14") (pintype "passive"))
      (node (ref "RY19") (pin "14") (pintype "passive"))
      (node (ref "RY2") (pin "14") (pintype "passive"))
      (node (ref "RY20") (pin "14") (pintype "passive"))
      (node (ref "RY21") (pin "14") (pintype "passive"))
      (node (ref "RY22") (pin "14") (pintype "passive"))
      (node (ref "RY23") (pin "14") (pintype "passive"))
      (node (ref "RY24") (pin "14") (pintype "passive"))
      (node (ref "RY25") (pin "14") (pintype "passive"))
      (node (ref "RY26") (pin "14") (pintype "passive"))
      (node (ref "RY27") (pin "14") (pintype "passive"))
      (node (ref "RY28") (pin "14") (pintype "passive"))
      (node (ref "RY29") (pin "14") (pintype "passive"))
      (node (ref "RY3") (pin "14") (pintype "passive"))
      (node (ref "RY30") (pin "14") (pintype "passive"))
      (node (ref "RY31") (pin "14") (pintype "passive"))
      (node (ref "RY32") (pin "14") (pintype "passive"))
      (node (ref "RY33") (pin "14") (pintype "passive"))
      (node (ref "RY34") (pin "14") (pintype "passive"))
      (node (ref "RY35") (pin "14") (pintype "passive"))
      (node (ref "RY36") (pin "14") (pintype "passive"))
      (node (ref "RY4") (pin "14") (pintype "passive"))
      (node (ref "RY5") (pin "14") (pintype "passive"))
      (node (ref "RY6") (pin "14") (pintype "passive"))
      (node (ref "RY7") (pin "14") (pintype "passive"))
      (node (ref "RY8") (pin "14") (pintype "passive"))
      (node (ref "RY9") (pin "14") (pintype "passive"))
    )
    (net (code "81") (name "GND") (class "Default")
      (node (ref "VT1") (pin "2") (pinfunction "E_2") (pintype "passive"))
      (node (ref "VT10") (pin "2") (pinfunction "E_2") (pintype "passive"))
      (node (ref "VT11") (pin "2") (pinfunction "E_2") (pintype "passive"))
      (node (ref "VT12") (pin "2") (pinfunction "E_2") (pintype "passive"))
      (node (ref "VT13") (pin "2") (pinfunction "E_2") (pintype "passive"))
      (node (ref "VT14") (pin "2") (pinfunction "E_2") (pintype "passive"))
      (node (ref "VT15") (pin "2") (pinfunction "E_2") (pintype "passive"))
      (node (ref "VT16") (pin "2") (pinfunction "E_2") (pintype "passive"))
      (node (ref "VT17") (pin "2") (pinfunction "E_2") (pintype "passive"))
      (node (ref "VT18") (pin "2") (pinfunction "E_2") (pintype "passive"))
      (node (ref "VT19") (pin "2") (pinfunction "E_2") (pintype "passive"))
      (node (ref "VT2") (pin "2") (pinfunction "E_2") (pintype "passive"))
      (node (ref "VT20") (pin "2") (pinfunction "E_2") (pintype "passive"))
      (node (ref "VT21") (pin "2") (pinfunction "E_2") (pintype "passive"))
      (node (ref "VT22") (pin "2") (pinfunction "E_2") (pintype "passive"))
      (node (ref "VT23") (pin "2") (pinfunction "E_2") (pintype "passive"))
      (node (ref "VT24") (pin "2") (pinfunction "E_2") (pintype "passive"))
      (node (ref "VT25") (pin "2") (pinfunction "E_2") (pintype "passive"))
      (node (ref "VT26") (pin "2") (pinfunction "E_2") (pintype "passive"))
      (node (ref "VT27") (pin "2") (pinfunction "E_2") (pintype "passive"))
      (node (ref "VT28") (pin "2") (pinfunction "E_2") (pintype "passive"))
      (node (ref "VT29") (pin "2") (pinfunction "E_2") (pintype "passive"))
      (node (ref "VT3") (pin "2") (pinfunction "E_2") (pintype "passive"))
      (node (ref "VT30") (pin "2") (pinfunction "E_2") (pintype "passive"))
      (node (ref "VT31") (pin "2") (pinfunction "E_2") (pintype "passive"))
      (node (ref "VT32") (pin "2") (pinfunction "E_2") (pintype "passive"))
      (node (ref "VT33") (pin "2") (pinfunction "E_2") (pintype "passive"))
      (node (ref "VT34") (pin "2") (pinfunction "E_2") (pintype "passive"))
      (node (ref "VT35") (pin "2") (pinfunction "E_2") (pintype "passive"))
      (node (ref "VT36") (pin "2") (pinfunction "E_2") (pintype "passive"))
      (node (ref "VT4") (pin "2") (pinfunction "E_2") (pintype "passive"))
      (node (ref "VT5") (pin "2") (pinfunction "E_2") (pintype "passive"))
      (node (ref "VT6") (pin "2") (pinfunction "E_2") (pintype "passive"))
      (node (ref "VT7") (pin "2") (pinfunction "E_2") (pintype "passive"))
      (node (ref "VT8") (pin "2") (pinfunction "E_2") (pintype "passive"))
      (node (ref "VT9") (pin "2") (pinfunction "E_2") (pintype "passive"))
    )
    (net (code "82") (name "Net-(VT1-C)") (class "Default")
      (node (ref "RY1") (pin "6") (pintype "passive"))
      (node (ref "VD1") (pin "1") (pinfunction "1_1") (pintype "passive"))
      (node (ref "VT1") (pin "3") (pinfunction "C_3") (pintype "passive"))
    )
    (net (code "83") (name "Net-(VT2-C)") (class "Default")
      (node (ref "RY2") (pin "6") (pintype "passive"))
      (node (ref "VD2") (pin "1") (pinfunction "1_1") (pintype "passive"))
      (node (ref "VT2") (pin "3") (pinfunction "C_3") (pintype "passive"))
    )
    (net (code "84") (name "Net-(VT3-C)") (class "Default")
      (node (ref "RY3") (pin "6") (pintype "passive"))
      (node (ref "VD3") (pin "1") (pinfunction "1_1") (pintype "passive"))
      (node (ref "VT3") (pin "3") (pinfunction "C_3") (pintype "passive"))
    )
    (net (code "85") (name "Net-(VT4-C)") (class "Default")
      (node (ref "RY4") (pin "6") (pintype "passive"))
      (node (ref "VD4") (pin "1") (pinfunction "1_1") (pintype "passive"))
      (node (ref "VT4") (pin "3") (pinfunction "C_3") (pintype "passive"))
    )
    (net (code "86") (name "Net-(VT5-C)") (class "Default")
      (node (ref "RY5") (pin "6") (pintype "passive"))
      (node (ref "VD5") (pin "1") (pinfunction "1_1") (pintype "passive"))
      (node (ref "VT5") (pin "3") (pinfunction "C_3") (pintype "passive"))
    )
    (net (code "87") (name "Net-(VT6-C)") (class "Default")
      (node (ref "RY6") (pin "6") (pintype "passive"))
      (node (ref "VD6") (pin "1") (pinfunction "1_1") (pintype "passive"))
      (node (ref "VT6") (pin "3") (pinfunction "C_3") (pintype "passive"))
    )
    (net (code "88") (name "Net-(VT7-C)") (class "Default")
      (node (ref "RY7") (pin "6") (pintype "passive"))
      (node (ref "VD7") (pin "1") (pinfunction "1_1") (pintype "passive"))
      (node (ref "VT7") (pin "3") (pinfunction "C_3") (pintype "passive"))
    )
    (net (code "89") (name "Net-(VT8-C)") (class "Default")
      (node (ref "RY8") (pin "6") (pintype "passive"))
      (node (ref "VD8") (pin "1") (pinfunction "1_1") (pintype "passive"))
      (node (ref "VT8") (pin "3") (pinfunction "C_3") (pintype "passive"))
    )
    (net (code "90") (name "Net-(VT9-C)") (class "Default")
      (node (ref "RY9") (pin "6") (pintype "passive"))
      (node (ref "VD9") (pin "1") (pinfunction "1_1") (pintype "passive"))
      (node (ref "VT9") (pin "3") (pinfunction "C_3") (pintype "passive"))
    )
    (net (code "91") (name "Net-(VT10-C)") (class "Default")
      (node (ref "RY10") (pin "6") (pintype "passive"))
      (node (ref "VD10") (pin "1") (pinfunction "1_1") (pintype "passive"))
      (node (ref "VT10") (pin "3") (pinfunction "C_3") (pintype "passive"))
    )
    (net (code "92") (name "Net-(VT11-C)") (class "Default")
      (node (ref "RY11") (pin "6") (pintype "passive"))
      (node (ref "VD11") (pin "1") (pinfunction "1_1") (pintype "passive"))
      (node (ref "VT11") (pin "3") (pinfunction "C_3") (pintype "passive"))
    )
    (net (code "93") (name "Net-(VT12-C)") (class "Default")
      (node (ref "RY12") (pin "6") (pintype "passive"))
      (node (ref "VD12") (pin "1") (pinfunction "1_1") (pintype "passive"))
      (node (ref "VT12") (pin "3") (pinfunction "C_3") (pintype "passive"))
    )
    (net (code "94") (name "Net-(VT13-C)") (class "Default")
      (node (ref "RY13") (pin "6") (pintype "passive"))
      (node (ref "VD18") (pin "1") (pinfunction "1_1") (pintype "passive"))
      (node (ref "VT13") (pin "3") (pinfunction "C_3") (pintype "passive"))
    )
    (net (code "95") (name "Net-(VT14-C)") (class "Default")
      (node (ref "RY14") (pin "6") (pintype "passive"))
      (node (ref "VD13") (pin "1") (pinfunction "1_1") (pintype "passive"))
      (node (ref "VT14") (pin "3") (pinfunction "C_3") (pintype "passive"))
    )
    (net (code "96") (name "Net-(VT15-C)") (class "Default")
      (node (ref "RY15") (pin "6") (pintype "passive"))
      (node (ref "VD14") (pin "1") (pinfunction "1_1") (pintype "passive"))
      (node (ref "VT15") (pin "3") (pinfunction "C_3") (pintype "passive"))
    )
    (net (code "97") (name "Net-(VT16-C)") (class "Default")
      (node (ref "RY16") (pin "6") (pintype "passive"))
      (node (ref "VD15") (pin "1") (pinfunction "1_1") (pintype "passive"))
      (node (ref "VT16") (pin "3") (pinfunction "C_3") (pintype "passive"))
    )
    (net (code "98") (name "Net-(VT17-C)") (class "Default")
      (node (ref "RY17") (pin "6") (pintype "passive"))
      (node (ref "VD16") (pin "1") (pinfunction "1_1") (pintype "passive"))
      (node (ref "VT17") (pin "3") (pinfunction "C_3") (pintype "passive"))
    )
    (net (code "99") (name "Net-(VT18-C)") (class "Default")
      (node (ref "RY18") (pin "6") (pintype "passive"))
      (node (ref "VD17") (pin "1") (pinfunction "1_1") (pintype "passive"))
      (node (ref "VT18") (pin "3") (pinfunction "C_3") (pintype "passive"))
    )
    (net (code "100") (name "Net-(VT19-C)") (class "Default")
      (node (ref "RY19") (pin "6") (pintype "passive"))
      (node (ref "VD19") (pin "1") (pinfunction "1_1") (pintype "passive"))
      (node (ref "VT19") (pin "3") (pinfunction "C_3") (pintype "passive"))
    )
    (net (code "101") (name "Net-(VT20-C)") (class "Default")
      (node (ref "RY20") (pin "6") (pintype "passive"))
      (node (ref "VD20") (pin "1") (pinfunction "1_1") (pintype "passive"))
      (node (ref "VT20") (pin "3") (pinfunction "C_3") (pintype "passive"))
    )
    (net (code "102") (name "Net-(VT21-C)") (class "Default")
      (node (ref "RY21") (pin "6") (pintype "passive"))
      (node (ref "VD21") (pin "1") (pinfunction "1_1") (pintype "passive"))
      (node (ref "VT21") (pin "3") (pinfunction "C_3") (pintype "passive"))
    )
    (net (code "103") (name "Net-(VT22-C)") (class "Default")
      (node (ref "RY22") (pin "6") (pintype "passive"))
      (node (ref "VD22") (pin "1") (pinfunction "1_1") (pintype "passive"))
      (node (ref "VT22") (pin "3") (pinfunction "C_3") (pintype "passive"))
    )
    (net (code "104") (name "Net-(VT23-C)") (class "Default")
      (node (ref "RY23") (pin "6") (pintype "passive"))
      (node (ref "VD23") (pin "1") (pinfunction "1_1") (pintype "passive"))
      (node (ref "VT23") (pin "3") (pinfunction "C_3") (pintype "passive"))
    )
    (net (code "105") (name "Net-(VT24-C)") (class "Default")
      (node (ref "RY24") (pin "6") (pintype "passive"))
      (node (ref "VD24") (pin "1") (pinfunction "1_1") (pintype "passive"))
      (node (ref "VT24") (pin "3") (pinfunction "C_3") (pintype "passive"))
    )
    (net (code "106") (name "Net-(VT25-C)") (class "Default")
      (node (ref "RY25") (pin "6") (pintype "passive"))
      (node (ref "VD25") (pin "1") (pinfunction "1_1") (pintype "passive"))
      (node (ref "VT25") (pin "3") (pinfunction "C_3") (pintype "passive"))
    )
    (net (code "107") (name "Net-(VT26-C)") (class "Default")
      (node (ref "RY26") (pin "6") (pintype "passive"))
      (node (ref "VD26") (pin "1") (pinfunction "1_1") (pintype "passive"))
      (node (ref "VT26") (pin "3") (pinfunction "C_3") (pintype "passive"))
    )
    (net (code "108") (name "Net-(VT27-C)") (class "Default")
      (node (ref "RY27") (pin "6") (pintype "passive"))
      (node (ref "VD27") (pin "1") (pinfunction "1_1") (pintype "passive"))
      (node (ref "VT27") (pin "3") (pinfunction "C_3") (pintype "passive"))
    )
    (net (code "109") (name "Net-(VT28-C)") (class "Default")
      (node (ref "RY28") (pin "6") (pintype "passive"))
      (node (ref "VD28") (pin "1") (pinfunction "1_1") (pintype "passive"))
      (node (ref "VT28") (pin "3") (pinfunction "C_3") (pintype "passive"))
    )
    (net (code "110") (name "Net-(VT29-C)") (class "Default")
      (node (ref "RY29") (pin "6") (pintype "passive"))
      (node (ref "VD29") (pin "1") (pinfunction "1_1") (pintype "passive"))
      (node (ref "VT29") (pin "3") (pinfunction "C_3") (pintype "passive"))
    )
    (net (code "111") (name "Net-(VT30-C)") (class "Default")
      (node (ref "RY30") (pin "6") (pintype "passive"))
      (node (ref "VD30") (pin "1") (pinfunction "1_1") (pintype "passive"))
      (node (ref "VT30") (pin "3") (pinfunction "C_3") (pintype "passive"))
    )
    (net (code "112") (name "Net-(VT31-C)") (class "Default")
      (node (ref "RY31") (pin "6") (pintype "passive"))
      (node (ref "VD31") (pin "1") (pinfunction "1_1") (pintype "passive"))
      (node (ref "VT31") (pin "3") (pinfunction "C_3") (pintype "passive"))
    )
    (net (code "113") (name "Net-(VT32-C)") (class "Default")
      (node (ref "RY32") (pin "6") (pintype "passive"))
      (node (ref "VD32") (pin "1") (pinfunction "1_1") (pintype "passive"))
      (node (ref "VT32") (pin "3") (pinfunction "C_3") (pintype "passive"))
    )
    (net (code "114") (name "Net-(VT33-C)") (class "Default")
      (node (ref "RY33") (pin "6") (pintype "passive"))
      (node (ref "VD33") (pin "1") (pinfunction "1_1") (pintype "passive"))
      (node (ref "VT33") (pin "3") (pinfunction "C_3") (pintype "passive"))
    )
    (net (code "115") (name "Net-(VT34-C)") (class "Default")
      (node (ref "RY34") (pin "6") (pintype "passive"))
      (node (ref "VD34") (pin "1") (pinfunction "1_1") (pintype "passive"))
      (node (ref "VT34") (pin "3") (pinfunction "C_3") (pintype "passive"))
    )
    (net (code "116") (name "Net-(VT35-C)") (class "Default")
      (node (ref "RY35") (pin "6") (pintype "passive"))
      (node (ref "VD35") (pin "1") (pinfunction "1_1") (pintype "passive"))
      (node (ref "VT35") (pin "3") (pinfunction "C_3") (pintype "passive"))
    )
    (net (code "117") (name "Net-(VT36-C)") (class "Default")
      (node (ref "RY36") (pin "6") (pintype "passive"))
      (node (ref "VD36") (pin "1") (pinfunction "1_1") (pintype "passive"))
      (node (ref "VT36") (pin "3") (pinfunction "C_3") (pintype "passive"))
    )
  )
)
